# LED.net
KiCad netlist of a schematic drawn in Altium Designer
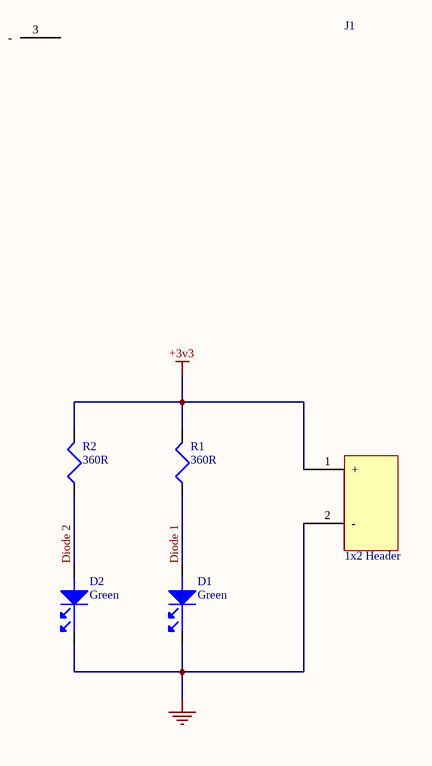
[diagram p0: LED.SchDoc]

(export (version "E")
  (design (tool "Eeschema 10.0.6"))
  (components
    (comp (ref "D1")
      (value "Green")
      (footprint "LED0603G - duplicate")
      (description "LED GREEN CLEAR CHIP 0603 SMD")
      (fields
        (field (name "MANUFACTURER") "Visual Communications")
        (field (name "MANUFACTURER PART NUMBER") "LSM0603453V")
      )
      (libsource (lib "LED_Schlib") (part "LSM0603453V"))
    )
    (comp (ref "D2")
      (value "Green")
      (footprint "LED0603G - duplicate")
      (description "LED GREEN CLEAR CHIP 0603 SMD")
      (fields
        (field (name "MANUFACTURER") "Visual Communications")
        (field (name "MANUFACTURER PART NUMBER") "LSM0603453V")
      )
      (libsource (lib "LED_Schlib") (part "LSM0603453V"))
    )
    (comp (ref "J1")
      (value "1x2 Header")
      (footprint "HDR1x2")
      (description "CONN HEADER VERT 2POS 2.54MM")
      (fields (field (name "MANUFACTURER") "Molex") (field (name "MANUFACTURER PART NUMBER") "22-27-2021"))
      (libsource (lib "LED_Schlib") (part "22-27-2021"))
    )
    (comp (ref "R1")
      (value "360R")
      (footprint "R0805")
      (description "RES SMD 360 OHM 0.1% 1/8W 0805")
      (fields
        (field (name "MANUFACTURER") "Yageo")
        (field (name "MANUFACTURER PART NUMBER") "RT0805BRD07360RL")
      )
      (libsource (lib "LED_Schlib") (part "RT0805BRD07360RL"))
    )
    (comp (ref "R2")
      (value "360R")
      (footprint "R0805")
      (description "RES SMD 360 OHM 0.1% 1/8W 0805")
      (fields
        (field (name "MANUFACTURER") "Yageo")
        (field (name "MANUFACTURER PART NUMBER") "RT0805BRD07360RL")
      )
      (libsource (lib "LED_Schlib") (part "RT0805BRD07360RL"))
    )
  )
  (nets
    (net (code "1") (name "+3v3") (class "Default")
      (node (ref "J1") (pin "1") (pinfunction "+_1") (pintype "passive"))
      (node (ref "R1") (pin "2") (pinfunction "2_2") (pintype "passive"))
      (node (ref "R2") (pin "2") (pinfunction "2_2") (pintype "passive"))
    )
    (net (code "2") (name "/Diode 1") (class "Default")
      (node (ref "D1") (pin "2") (pinfunction "2_2") (pintype "passive"))
      (node (ref "R1") (pin "1") (pinfunction "1_1") (pintype "passive"))
    )
    (net (code "3") (name "/Diode 2") (class "Default")
      (node (ref "D2") (pin "2") (pinfunction "2_2") (pintype "passive"))
      (node (ref "R2") (pin "1") (pinfunction "1_1") (pintype "passive"))
    )
    (net (code "4") (name "GND") (class "Default")
      (node (ref "D1") (pin "1") (pinfunction "1_1") (pintype "passive"))
      (node (ref "D2") (pin "1") (pinfunction "1_1") (pintype "passive"))
      (node (ref "J1") (pin "2") (pinfunction "-_2") (pintype "passive"))
    )
    (net (code "5") (name "unconnected-(J1---Pad3)") (class "Default")
      (node (ref "J1") (pin "3") (pinfunction "-_3") (pintype "passive"))
    )
  )
)
